# V1_0.net
KiCad netlist of a schematic drawn in EasyEDA Pro
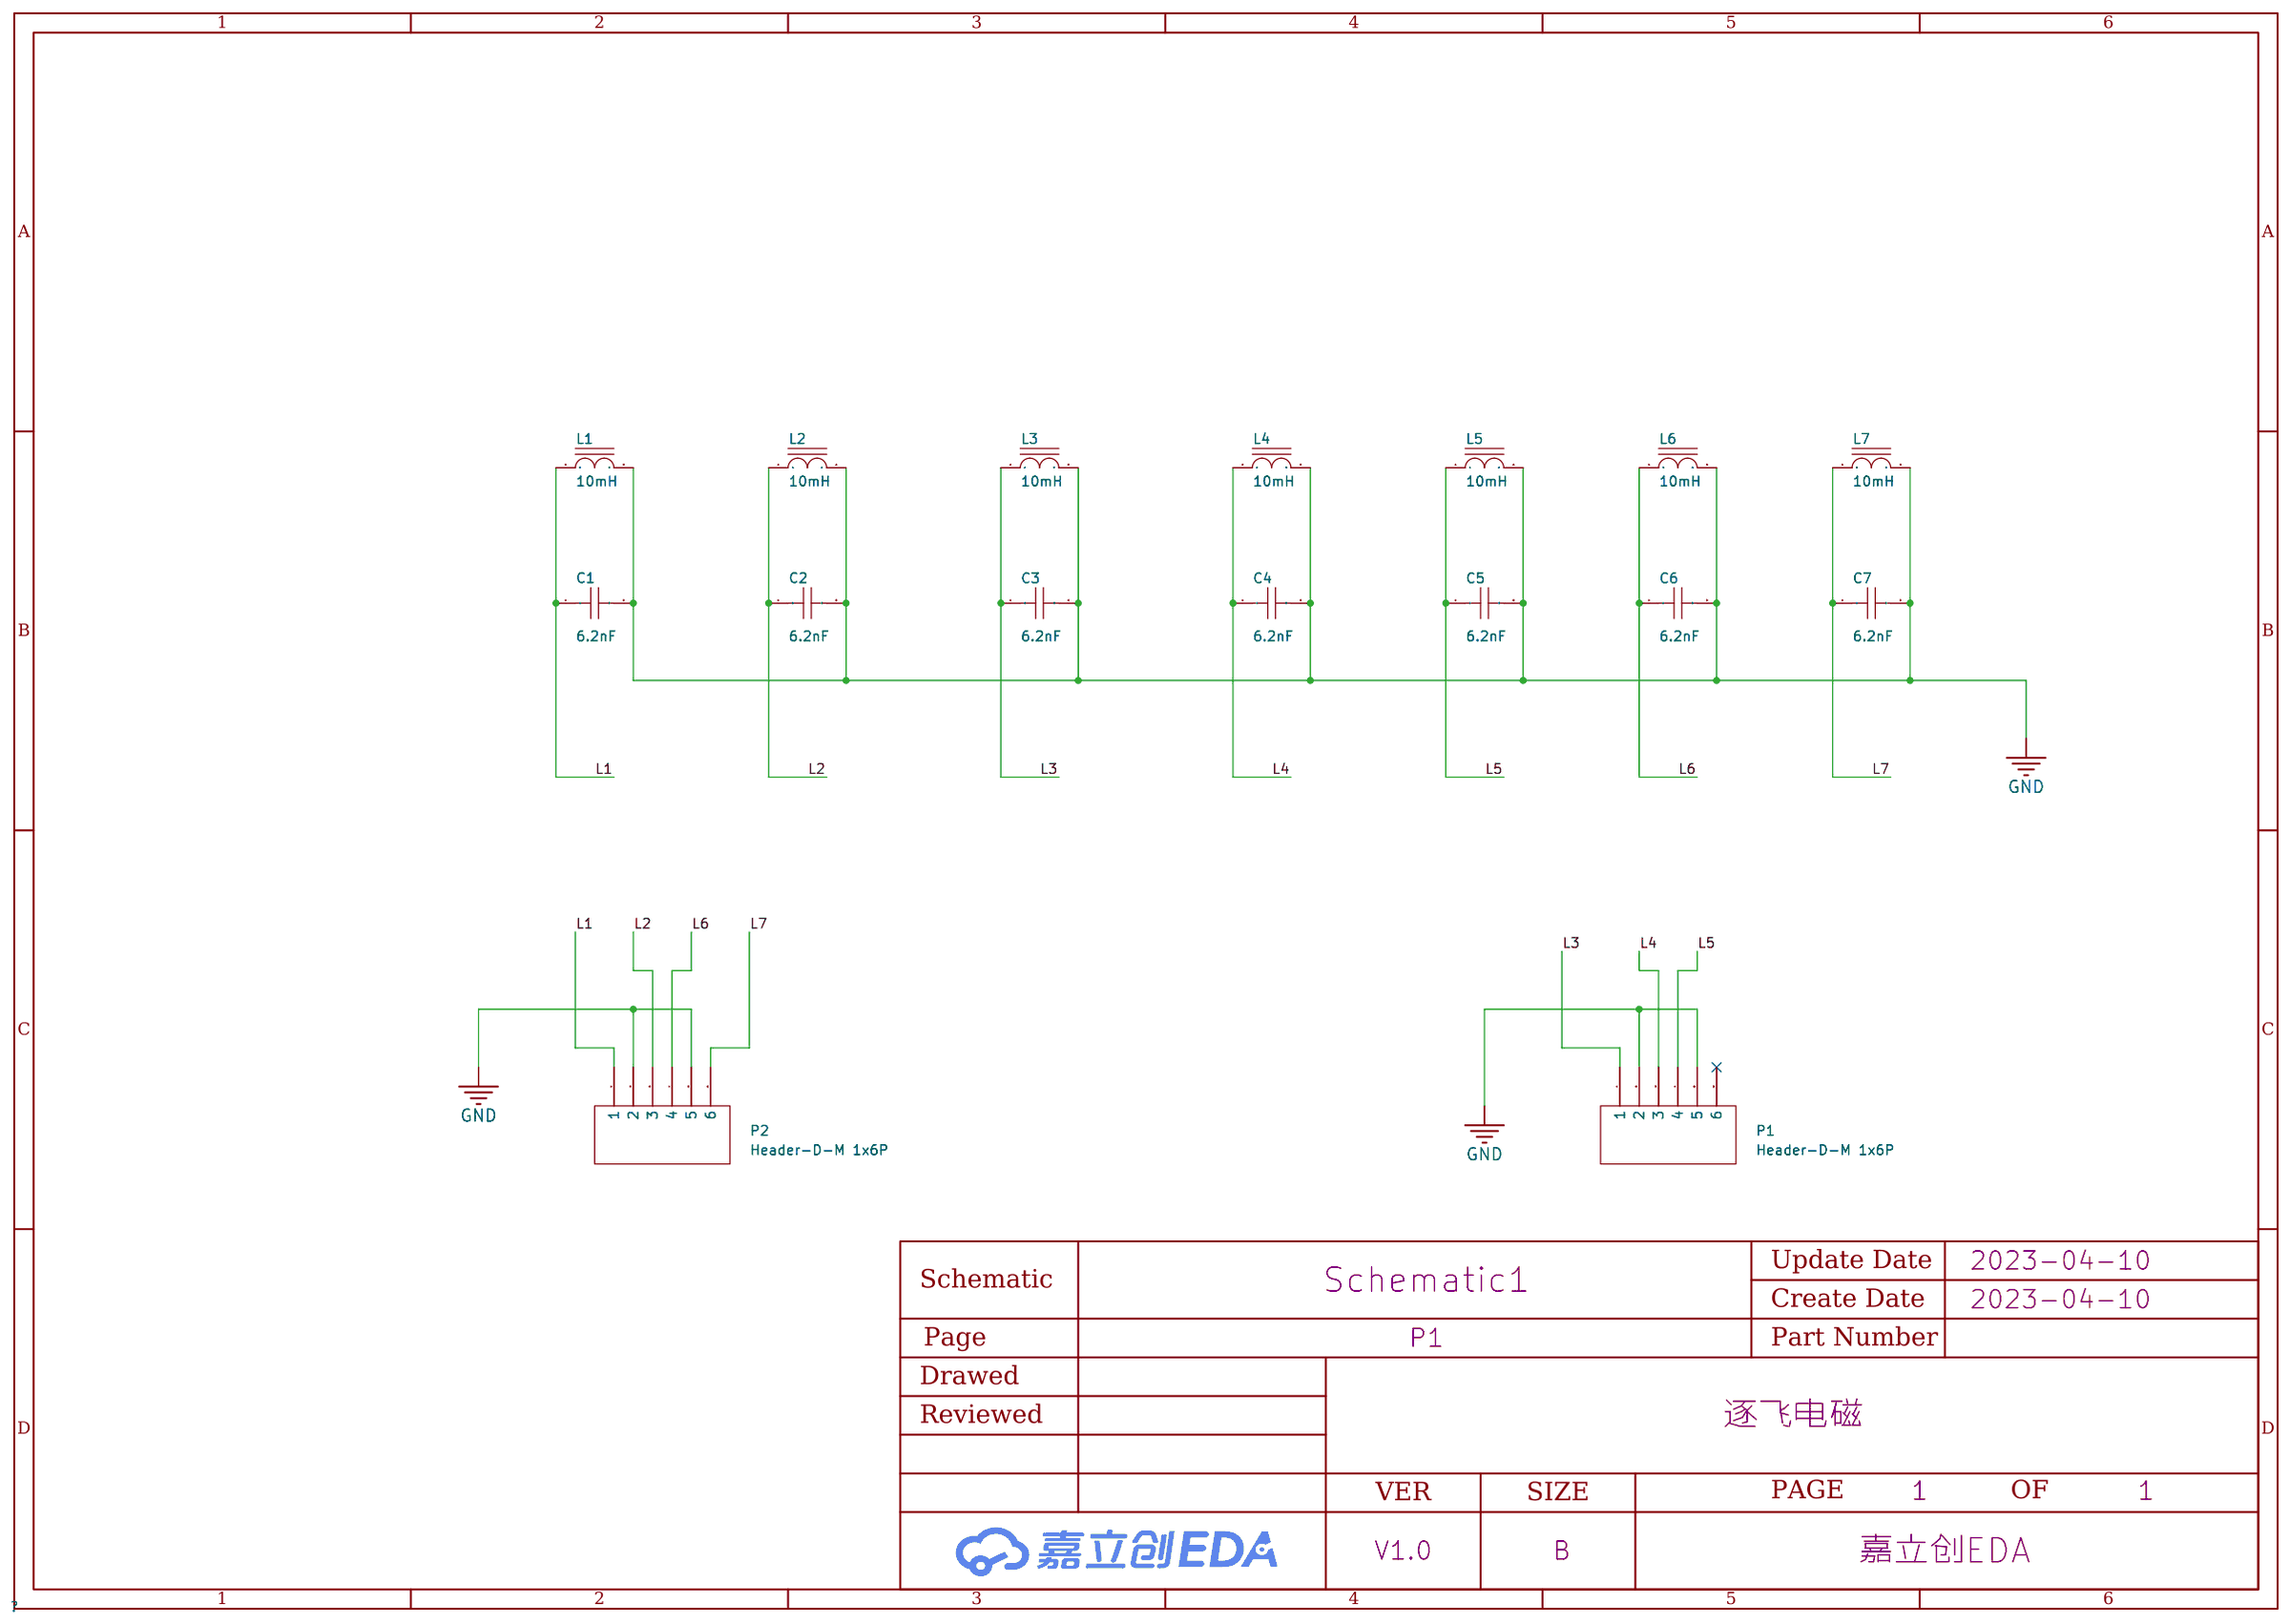
[diagram p0: schematic sheet]

(export (version "E")
  (design (tool "Eeschema 10.0.6"))
  (components
    (comp (ref "C1")
      (value "6.2nF")
      (footprint "easyedapro:C0805")
      (description "容值:6.2nF;精度:±10%;额定电压:50V;材质(温度系数):X7R;额定电压(VAC):-;")
      (fields (field (name "Manufacturer Part") "0805B622K500NT") (field (name "Manufacturer") "FH(风华)"))
      (libsource (lib "easyedapro") (part "0805B622K500NT"))
    )
    (comp (ref "C2")
      (value "6.2nF")
      (footprint "easyedapro:C0805")
      (description "容值:6.2nF;精度:±10%;额定电压:50V;材质(温度系数):X7R;额定电压(VAC):-;")
      (fields (field (name "Manufacturer Part") "0805B622K500NT") (field (name "Manufacturer") "FH(风华)"))
      (libsource (lib "easyedapro") (part "0805B622K500NT"))
    )
    (comp (ref "C3")
      (value "6.2nF")
      (footprint "easyedapro:C0805")
      (description "容值:6.2nF;精度:±10%;额定电压:50V;材质(温度系数):X7R;额定电压(VAC):-;")
      (fields (field (name "Manufacturer Part") "0805B622K500NT") (field (name "Manufacturer") "FH(风华)"))
      (libsource (lib "easyedapro") (part "0805B622K500NT"))
    )
    (comp (ref "C4")
      (value "6.2nF")
      (footprint "easyedapro:C0805")
      (description "容值:6.2nF;精度:±10%;额定电压:50V;材质(温度系数):X7R;额定电压(VAC):-;")
      (fields (field (name "Manufacturer Part") "0805B622K500NT") (field (name "Manufacturer") "FH(风华)"))
      (libsource (lib "easyedapro") (part "0805B622K500NT"))
    )
    (comp (ref "C5")
      (value "6.2nF")
      (footprint "easyedapro:C0805")
      (description "容值:6.2nF;精度:±10%;额定电压:50V;材质(温度系数):X7R;额定电压(VAC):-;")
      (fields (field (name "Manufacturer Part") "0805B622K500NT") (field (name "Manufacturer") "FH(风华)"))
      (libsource (lib "easyedapro") (part "0805B622K500NT"))
    )
    (comp (ref "C6")
      (value "6.2nF")
      (footprint "easyedapro:C0805")
      (description "容值:6.2nF;精度:±10%;额定电压:50V;材质(温度系数):X7R;额定电压(VAC):-;")
      (fields (field (name "Manufacturer Part") "0805B622K500NT") (field (name "Manufacturer") "FH(风华)"))
      (libsource (lib "easyedapro") (part "0805B622K500NT"))
    )
    (comp (ref "C7")
      (value "6.2nF")
      (footprint "easyedapro:C0805")
      (description "容值:6.2nF;精度:±10%;额定电压:50V;材质(温度系数):X7R;额定电压(VAC):-;")
      (fields (field (name "Manufacturer Part") "0805B622K500NT") (field (name "Manufacturer") "FH(风华)"))
      (libsource (lib "easyedapro") (part "0805B622K500NT"))
    )
    (comp (ref "L1")
      (value "10mH")
      (footprint "easyedapro:LD8x10")
      (libsource (lib "easyedapro") (part "Ind-Power"))
    )
    (comp (ref "L2")
      (value "10mH")
      (footprint "easyedapro:LD8x10")
      (libsource (lib "easyedapro") (part "Ind-Power"))
    )
    (comp (ref "L3")
      (value "10mH")
      (footprint "easyedapro:LD8x10")
      (libsource (lib "easyedapro") (part "Ind-Power"))
    )
    (comp (ref "L4")
      (value "10mH")
      (footprint "easyedapro:LD8x10")
      (libsource (lib "easyedapro") (part "Ind-Power"))
    )
    (comp (ref "L5")
      (value "10mH")
      (footprint "easyedapro:LD8x10")
      (libsource (lib "easyedapro") (part "Ind-Power"))
    )
    (comp (ref "L6")
      (value "10mH")
      (footprint "easyedapro:LD8x10")
      (libsource (lib "easyedapro") (part "Ind-Power"))
    )
    (comp (ref "L7")
      (value "10mH")
      (footprint "easyedapro:LD8x10")
      (libsource (lib "easyedapro") (part "Ind-Power"))
    )
    (comp (ref "P1")
      (value "Header-D-M 1x6P")
      (footprint "easyedapro:HDR1X6-M")
      (libsource (lib "easyedapro") (part "Header-D-M 1x6P"))
    )
    (comp (ref "P2")
      (value "Header-D-M 1x6P")
      (footprint "easyedapro:HDR1X6-M")
      (libsource (lib "easyedapro") (part "Header-D-M 1x6P"))
    )
  )
  (nets
    (net (code "1") (name "/L1") (class "Default")
      (node (ref "C1") (pin "1") (pinfunction "1_1") (pintype "input"))
      (node (ref "L1") (pin "1") (pinfunction "1_1") (pintype "input"))
      (node (ref "P2") (pin "1") (pinfunction "1_1") (pintype "input"))
    )
    (net (code "2") (name "/L2") (class "Default")
      (node (ref "C2") (pin "1") (pinfunction "1_1") (pintype "input"))
      (node (ref "L2") (pin "1") (pinfunction "1_1") (pintype "input"))
      (node (ref "P2") (pin "3") (pinfunction "3_3") (pintype "input"))
    )
    (net (code "3") (name "/L3") (class "Default")
      (node (ref "C3") (pin "1") (pinfunction "1_1") (pintype "input"))
      (node (ref "L3") (pin "1") (pinfunction "1_1") (pintype "input"))
      (node (ref "P1") (pin "1") (pinfunction "1_1") (pintype "input"))
    )
    (net (code "4") (name "/L4") (class "Default")
      (node (ref "C4") (pin "1") (pinfunction "1_1") (pintype "input"))
      (node (ref "L4") (pin "1") (pinfunction "1_1") (pintype "input"))
      (node (ref "P1") (pin "3") (pinfunction "3_3") (pintype "input"))
    )
    (net (code "5") (name "/L5") (class "Default")
      (node (ref "C5") (pin "1") (pinfunction "1_1") (pintype "input"))
      (node (ref "L5") (pin "1") (pinfunction "1_1") (pintype "input"))
      (node (ref "P1") (pin "4") (pinfunction "4_4") (pintype "input"))
    )
    (net (code "6") (name "/L6") (class "Default")
      (node (ref "C6") (pin "1") (pinfunction "1_1") (pintype "input"))
      (node (ref "L6") (pin "1") (pinfunction "1_1") (pintype "input"))
      (node (ref "P2") (pin "4") (pinfunction "4_4") (pintype "input"))
    )
    (net (code "7") (name "/L7") (class "Default")
      (node (ref "C7") (pin "1") (pinfunction "1_1") (pintype "input"))
      (node (ref "L7") (pin "1") (pinfunction "1_1") (pintype "input"))
      (node (ref "P2") (pin "6") (pinfunction "6_6") (pintype "input"))
    )
    (net (code "8") (name "GND") (class "Default")
      (node (ref "C1") (pin "2") (pinfunction "2_2") (pintype "input"))
      (node (ref "C2") (pin "2") (pinfunction "2_2") (pintype "input"))
      (node (ref "C3") (pin "2") (pinfunction "2_2") (pintype "input"))
      (node (ref "C4") (pin "2") (pinfunction "2_2") (pintype "input"))
      (node (ref "C5") (pin "2") (pinfunction "2_2") (pintype "input"))
      (node (ref "C6") (pin "2") (pinfunction "2_2") (pintype "input"))
      (node (ref "C7") (pin "2") (pinfunction "2_2") (pintype "input"))
      (node (ref "L1") (pin "2") (pinfunction "2_2") (pintype "input"))
      (node (ref "L2") (pin "2") (pinfunction "2_2") (pintype "input"))
      (node (ref "L3") (pin "2") (pinfunction "2_2") (pintype "input"))
      (node (ref "L4") (pin "2") (pinfunction "2_2") (pintype "input"))
      (node (ref "L5") (pin "2") (pinfunction "2_2") (pintype "input"))
      (node (ref "L6") (pin "2") (pinfunction "2_2") (pintype "input"))
      (node (ref "L7") (pin "2") (pinfunction "2_2") (pintype "input"))
      (node (ref "P1") (pin "2") (pinfunction "2_2") (pintype "input"))
      (node (ref "P1") (pin "5") (pinfunction "5_5") (pintype "input"))
      (node (ref "P2") (pin "2") (pinfunction "2_2") (pintype "input"))
      (node (ref "P2") (pin "5") (pinfunction "5_5") (pintype "input"))
    )
    (net (code "9") (name "unconnected-(P1-Pad6)") (class "Default")
      (node (ref "P1") (pin "6") (pinfunction "6_6") (pintype "input+no_connect"))
    )
  )
)
